# control.net
KiCad netlist of a schematic drawn in EAGLE
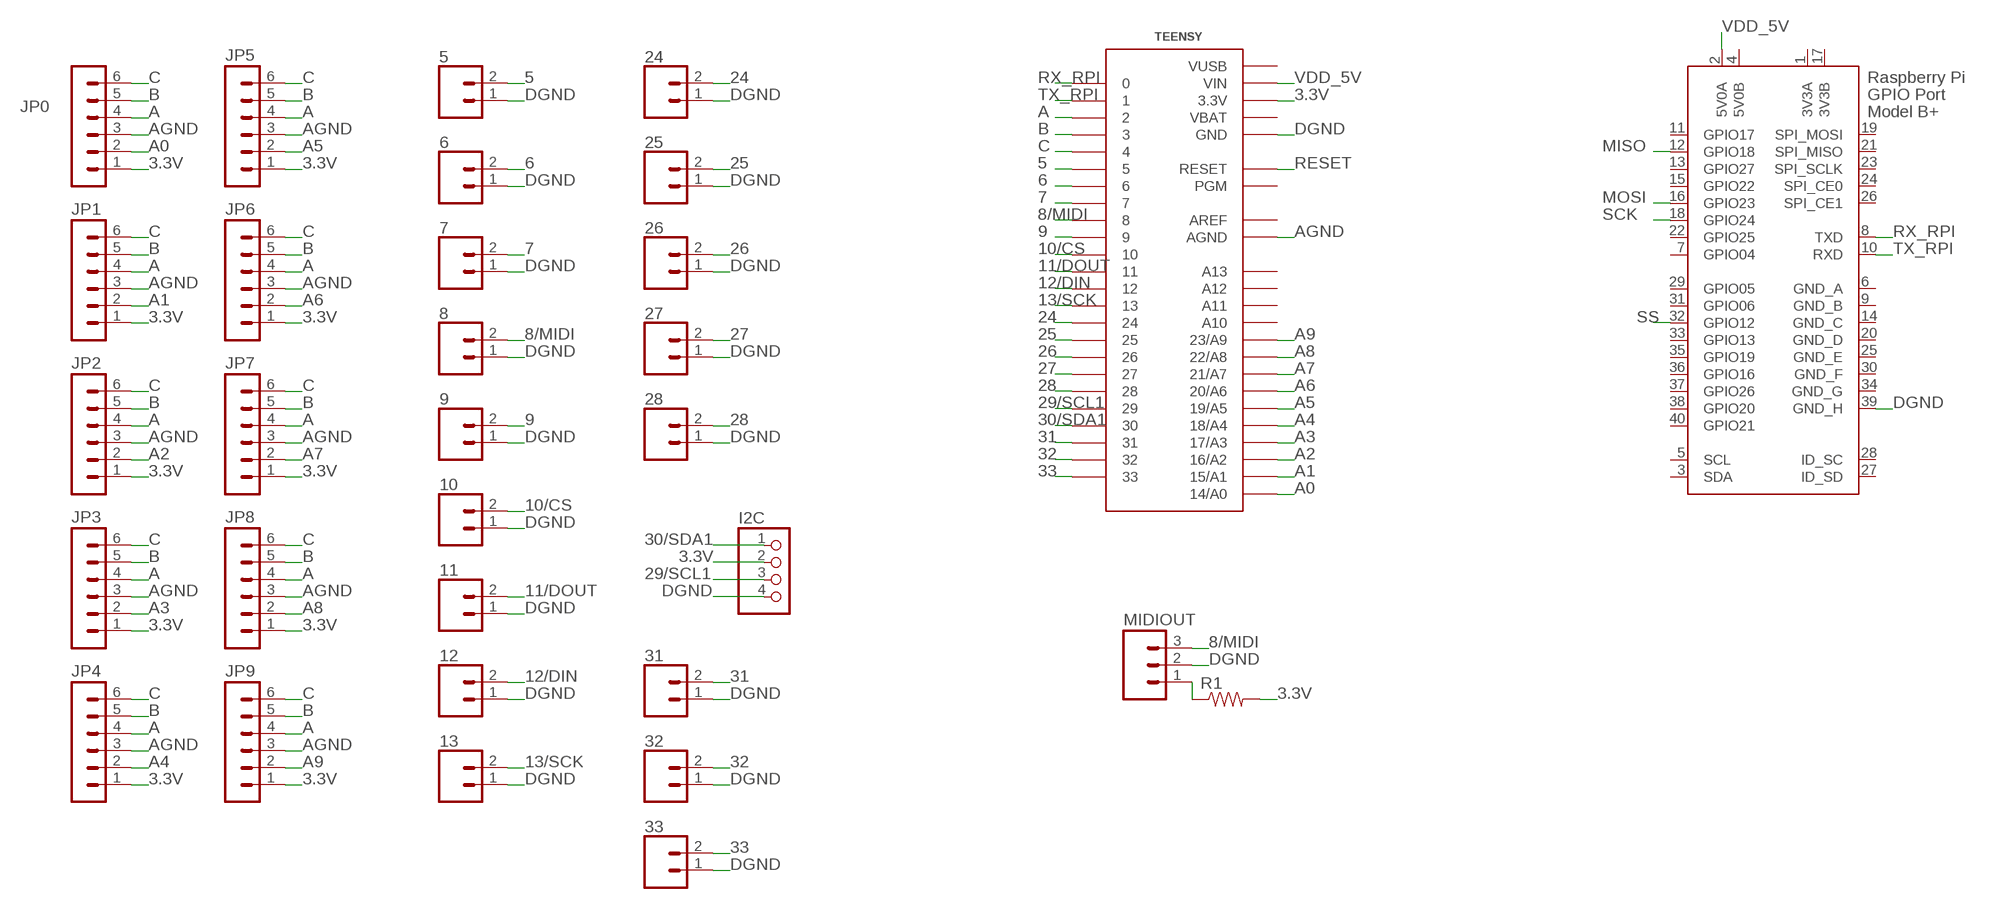
[diagram p0: schematic, sheet 1]

(export (version "E")
  (design (tool "Eeschema 10.0.6"))
  (components
    (comp (ref "5")
      (value "CONN_02")
      (footprint "eagle-import:1X02")
      (libsource (lib "eagle-import") (part "CONN_02"))
    )
    (comp (ref "6")
      (value "CONN_02")
      (footprint "eagle-import:1X02")
      (libsource (lib "eagle-import") (part "CONN_02"))
    )
    (comp (ref "7")
      (value "CONN_02")
      (footprint "eagle-import:1X02")
      (libsource (lib "eagle-import") (part "CONN_02"))
    )
    (comp (ref "8")
      (value "CONN_02")
      (footprint "eagle-import:1X02")
      (libsource (lib "eagle-import") (part "CONN_02"))
    )
    (comp (ref "9")
      (value "CONN_02")
      (footprint "eagle-import:1X02")
      (libsource (lib "eagle-import") (part "CONN_02"))
    )
    (comp (ref "10")
      (value "CONN_02")
      (footprint "eagle-import:1X02")
      (libsource (lib "eagle-import") (part "CONN_02"))
    )
    (comp (ref "11")
      (value "CONN_02")
      (footprint "eagle-import:1X02")
      (libsource (lib "eagle-import") (part "CONN_02"))
    )
    (comp (ref "12")
      (value "CONN_02")
      (footprint "eagle-import:1X02")
      (libsource (lib "eagle-import") (part "CONN_02"))
    )
    (comp (ref "13")
      (value "CONN_02")
      (footprint "eagle-import:1X02")
      (libsource (lib "eagle-import") (part "CONN_02"))
    )
    (comp (ref "24")
      (value "CONN_02")
      (footprint "eagle-import:1X02")
      (libsource (lib "eagle-import") (part "CONN_02"))
    )
    (comp (ref "25")
      (value "CONN_02")
      (footprint "eagle-import:1X02")
      (libsource (lib "eagle-import") (part "CONN_02"))
    )
    (comp (ref "26")
      (value "CONN_02")
      (footprint "eagle-import:1X02")
      (libsource (lib "eagle-import") (part "CONN_02"))
    )
    (comp (ref "27")
      (value "CONN_02")
      (footprint "eagle-import:1X02")
      (libsource (lib "eagle-import") (part "CONN_02"))
    )
    (comp (ref "28")
      (value "CONN_02")
      (footprint "eagle-import:1X02")
      (libsource (lib "eagle-import") (part "CONN_02"))
    )
    (comp (ref "31")
      (value "CONN_02")
      (footprint "eagle-import:1X02")
      (libsource (lib "eagle-import") (part "CONN_02"))
    )
    (comp (ref "32")
      (value "CONN_02")
      (footprint "eagle-import:1X02")
      (libsource (lib "eagle-import") (part "CONN_02"))
    )
    (comp (ref "33")
      (value "CONN_02")
      (footprint "eagle-import:1X02")
      (libsource (lib "eagle-import") (part "CONN_02"))
    )
    (comp (ref "I2C")
      (value "PINHD-1X4")
      (footprint "eagle-import:1X04")
      (libsource (lib "eagle-import") (part "PINHD-1X4"))
    )
    (comp (ref "JP0")
      (value "MA06-1")
      (footprint "eagle-import:MA06-1")
      (libsource (lib "eagle-import") (part "MA06-1"))
    )
    (comp (ref "JP1")
      (value "MA06-1")
      (footprint "eagle-import:MA06-1")
      (libsource (lib "eagle-import") (part "MA06-1"))
    )
    (comp (ref "JP2")
      (value "MA06-1")
      (footprint "eagle-import:MA06-1")
      (libsource (lib "eagle-import") (part "MA06-1"))
    )
    (comp (ref "JP3")
      (value "MA06-1")
      (footprint "eagle-import:MA06-1")
      (libsource (lib "eagle-import") (part "MA06-1"))
    )
    (comp (ref "JP4")
      (value "MA06-1")
      (footprint "eagle-import:MA06-1")
      (libsource (lib "eagle-import") (part "MA06-1"))
    )
    (comp (ref "JP5")
      (value "MA06-1")
      (footprint "eagle-import:MA06-1")
      (libsource (lib "eagle-import") (part "MA06-1"))
    )
    (comp (ref "JP6")
      (value "MA06-1")
      (footprint "eagle-import:MA06-1")
      (libsource (lib "eagle-import") (part "MA06-1"))
    )
    (comp (ref "JP7")
      (value "MA06-1")
      (footprint "eagle-import:MA06-1")
      (libsource (lib "eagle-import") (part "MA06-1"))
    )
    (comp (ref "JP8")
      (value "MA06-1")
      (footprint "eagle-import:MA06-1")
      (libsource (lib "eagle-import") (part "MA06-1"))
    )
    (comp (ref "JP9")
      (value "MA06-1")
      (footprint "eagle-import:MA06-1")
      (libsource (lib "eagle-import") (part "MA06-1"))
    )
    (comp (ref "MIDIOUT")
      (value "M03PTH")
      (footprint "eagle-import:1X03")
      (libsource (lib "eagle-import") (part "M03PTH"))
    )
    (comp (ref "R1")
      (value "RESISTORAXIAL-0.3")
      (footprint "eagle-import:AXIAL-0.3")
      (libsource (lib "eagle-import") (part "RESISTORAXIAL-0.3"))
    )
    (comp (ref "TEENSY")
      (value "TEENSY_3.0_ALLPINS")
      (footprint "eagle-import:TEENSY_3.0_ALLPINS")
      (libsource (lib "eagle-import") (part "TEENSY_3.0_ALLPINS"))
    )
    (comp (ref "X1")
      (value "RASPI_BOARD_B+#_H")
      (footprint "eagle-import:RASPI_BOARD_B+HAT")
      (libsource (lib "eagle-import") (part "RASPI_BOARD_B+#_H"))
    )
  )
  (nets
    (net (code "1") (name "/3.3V") (class "Default")
      (node (ref "I2C") (pin "2") (pinfunction "2_2") (pintype "passive"))
      (node (ref "JP0") (pin "1") (pinfunction "1_1") (pintype "passive"))
      (node (ref "JP1") (pin "1") (pinfunction "1_1") (pintype "passive"))
      (node (ref "JP2") (pin "1") (pinfunction "1_1") (pintype "passive"))
      (node (ref "JP3") (pin "1") (pinfunction "1_1") (pintype "passive"))
      (node (ref "JP4") (pin "1") (pinfunction "1_1") (pintype "passive"))
      (node (ref "JP5") (pin "1") (pinfunction "1_1") (pintype "passive"))
      (node (ref "JP6") (pin "1") (pinfunction "1_1") (pintype "passive"))
      (node (ref "JP7") (pin "1") (pinfunction "1_1") (pintype "passive"))
      (node (ref "JP8") (pin "1") (pinfunction "1_1") (pintype "passive"))
      (node (ref "JP9") (pin "1") (pinfunction "1_1") (pintype "passive"))
      (node (ref "R1") (pin "P$2") (pinfunction "2_P$2") (pintype "passive"))
      (node (ref "TEENSY") (pin "3.3V") (pinfunction "3.3V_3.3V") (pintype "power_in"))
      (node (ref "TEENSY") (pin "3.3V1") (pinfunction "3.3V_3.3V1") (pintype "power_in"))
      (node (ref "TEENSY") (pin "3.3V2") (pinfunction "3.3V_3.3V2") (pintype "power_in"))
    )
    (net (code "2") (name "/3V3A") (class "Default")
      (node (ref "X1") (pin "1") (pinfunction "3V3A_1") (pintype "power_in"))
    )
    (net (code "3") (name "/3V3B") (class "Default")
      (node (ref "X1") (pin "17") (pinfunction "3V3B_17") (pintype "power_in"))
    )
    (net (code "4") (name "/5") (class "Default")
      (node (ref "5") (pin "2") (pinfunction "2_2") (pintype "passive"))
      (node (ref "TEENSY") (pin "5") (pinfunction "5_5") (pintype "bidirectional"))
    )
    (net (code "5") (name "/5V0B") (class "Default")
      (node (ref "X1") (pin "4") (pinfunction "5V0B_4") (pintype "power_in"))
    )
    (net (code "6") (name "/6") (class "Default")
      (node (ref "6") (pin "2") (pinfunction "2_2") (pintype "passive"))
      (node (ref "TEENSY") (pin "6") (pinfunction "6_6") (pintype "bidirectional"))
    )
    (net (code "7") (name "/7") (class "Default")
      (node (ref "7") (pin "2") (pinfunction "2_2") (pintype "passive"))
      (node (ref "TEENSY") (pin "7") (pinfunction "7_7") (pintype "bidirectional"))
    )
    (net (code "8") (name "/8{slash}MIDI") (class "Default")
      (node (ref "8") (pin "2") (pinfunction "2_2") (pintype "passive"))
      (node (ref "MIDIOUT") (pin "3") (pinfunction "3_3") (pintype "passive"))
      (node (ref "TEENSY") (pin "8") (pinfunction "8_8") (pintype "bidirectional"))
    )
    (net (code "9") (name "/9") (class "Default")
      (node (ref "9") (pin "2") (pinfunction "2_2") (pintype "passive"))
      (node (ref "TEENSY") (pin "9") (pinfunction "9_9") (pintype "bidirectional"))
    )
    (net (code "10") (name "/10{slash}CS") (class "Default")
      (node (ref "10") (pin "2") (pinfunction "2_2") (pintype "passive"))
      (node (ref "TEENSY") (pin "10") (pinfunction "10_10") (pintype "bidirectional"))
    )
    (net (code "11") (name "/11{slash}DOUT") (class "Default")
      (node (ref "11") (pin "2") (pinfunction "2_2") (pintype "passive"))
      (node (ref "TEENSY") (pin "11") (pinfunction "11_11") (pintype "bidirectional"))
    )
    (net (code "12") (name "/12{slash}DIN") (class "Default")
      (node (ref "12") (pin "2") (pinfunction "2_2") (pintype "passive"))
      (node (ref "TEENSY") (pin "12") (pinfunction "12_12") (pintype "bidirectional"))
    )
    (net (code "13") (name "/13{slash}SCK") (class "Default")
      (node (ref "13") (pin "2") (pinfunction "2_2") (pintype "passive"))
      (node (ref "TEENSY") (pin "13") (pinfunction "13_13") (pintype "bidirectional"))
    )
    (net (code "14") (name "/24") (class "Default")
      (node (ref "24") (pin "2") (pinfunction "2_2") (pintype "passive"))
      (node (ref "TEENSY") (pin "24") (pinfunction "24_24") (pintype "bidirectional"))
    )
    (net (code "15") (name "/25") (class "Default")
      (node (ref "25") (pin "2") (pinfunction "2_2") (pintype "passive"))
      (node (ref "TEENSY") (pin "25") (pinfunction "25_25") (pintype "bidirectional"))
    )
    (net (code "16") (name "/26") (class "Default")
      (node (ref "26") (pin "2") (pinfunction "2_2") (pintype "passive"))
      (node (ref "TEENSY") (pin "26") (pinfunction "26_26") (pintype "bidirectional"))
    )
    (net (code "17") (name "/27") (class "Default")
      (node (ref "27") (pin "2") (pinfunction "2_2") (pintype "passive"))
      (node (ref "TEENSY") (pin "27") (pinfunction "27_27") (pintype "bidirectional"))
    )
    (net (code "18") (name "/28") (class "Default")
      (node (ref "28") (pin "2") (pinfunction "2_2") (pintype "passive"))
      (node (ref "TEENSY") (pin "28") (pinfunction "28_28") (pintype "bidirectional"))
    )
    (net (code "19") (name "/29{slash}SCL1") (class "Default")
      (node (ref "I2C") (pin "3") (pinfunction "3_3") (pintype "passive"))
      (node (ref "TEENSY") (pin "29") (pinfunction "29_29") (pintype "bidirectional"))
    )
    (net (code "20") (name "/30{slash}SDA1") (class "Default")
      (node (ref "I2C") (pin "1") (pinfunction "1_1") (pintype "passive"))
      (node (ref "TEENSY") (pin "30") (pinfunction "30_30") (pintype "bidirectional"))
    )
    (net (code "21") (name "/31") (class "Default")
      (node (ref "31") (pin "2") (pinfunction "2_2") (pintype "passive"))
      (node (ref "TEENSY") (pin "31") (pinfunction "31_31") (pintype "bidirectional"))
    )
    (net (code "22") (name "/32") (class "Default")
      (node (ref "32") (pin "2") (pinfunction "2_2") (pintype "passive"))
      (node (ref "TEENSY") (pin "32") (pinfunction "32_32") (pintype "bidirectional"))
    )
    (net (code "23") (name "/33") (class "Default")
      (node (ref "33") (pin "2") (pinfunction "2_2") (pintype "passive"))
      (node (ref "TEENSY") (pin "33") (pinfunction "33_33") (pintype "bidirectional"))
    )
    (net (code "24") (name "/A") (class "Default")
      (node (ref "JP0") (pin "4") (pinfunction "4_4") (pintype "passive"))
      (node (ref "JP1") (pin "4") (pinfunction "4_4") (pintype "passive"))
      (node (ref "JP2") (pin "4") (pinfunction "4_4") (pintype "passive"))
      (node (ref "JP3") (pin "4") (pinfunction "4_4") (pintype "passive"))
      (node (ref "JP4") (pin "4") (pinfunction "4_4") (pintype "passive"))
      (node (ref "JP5") (pin "4") (pinfunction "4_4") (pintype "passive"))
      (node (ref "JP6") (pin "4") (pinfunction "4_4") (pintype "passive"))
      (node (ref "JP7") (pin "4") (pinfunction "4_4") (pintype "passive"))
      (node (ref "JP8") (pin "4") (pinfunction "4_4") (pintype "passive"))
      (node (ref "JP9") (pin "4") (pinfunction "4_4") (pintype "passive"))
      (node (ref "TEENSY") (pin "2") (pinfunction "2_2") (pintype "bidirectional"))
    )
    (net (code "25") (name "/A0") (class "Default")
      (node (ref "JP0") (pin "2") (pinfunction "2_2") (pintype "passive"))
      (node (ref "TEENSY") (pin "14/A0") (pinfunction "14/A0_14/A0") (pintype "bidirectional"))
    )
    (net (code "26") (name "/A1") (class "Default")
      (node (ref "JP1") (pin "2") (pinfunction "2_2") (pintype "passive"))
      (node (ref "TEENSY") (pin "15/A1") (pinfunction "15/A1_15/A1") (pintype "bidirectional"))
    )
    (net (code "27") (name "/A2") (class "Default")
      (node (ref "JP2") (pin "2") (pinfunction "2_2") (pintype "passive"))
      (node (ref "TEENSY") (pin "16/A2") (pinfunction "16/A2_16/A2") (pintype "bidirectional"))
    )
    (net (code "28") (name "/A3") (class "Default")
      (node (ref "JP3") (pin "2") (pinfunction "2_2") (pintype "passive"))
      (node (ref "TEENSY") (pin "17/A3") (pinfunction "17/A3_17/A3") (pintype "bidirectional"))
    )
    (net (code "29") (name "/A4") (class "Default")
      (node (ref "JP4") (pin "2") (pinfunction "2_2") (pintype "passive"))
      (node (ref "TEENSY") (pin "18/A4") (pinfunction "18/A4_18/A4") (pintype "bidirectional"))
    )
    (net (code "30") (name "/A5") (class "Default")
      (node (ref "JP5") (pin "2") (pinfunction "2_2") (pintype "passive"))
      (node (ref "TEENSY") (pin "19/A5") (pinfunction "19/A5_19/A5") (pintype "bidirectional"))
    )
    (net (code "31") (name "/A6") (class "Default")
      (node (ref "JP6") (pin "2") (pinfunction "2_2") (pintype "passive"))
      (node (ref "TEENSY") (pin "20/A6") (pinfunction "20/A6_20/A6") (pintype "bidirectional"))
    )
    (net (code "32") (name "/A7") (class "Default")
      (node (ref "JP7") (pin "2") (pinfunction "2_2") (pintype "passive"))
      (node (ref "TEENSY") (pin "21/A7") (pinfunction "21/A7_21/A7") (pintype "bidirectional"))
    )
    (net (code "33") (name "/A8") (class "Default")
      (node (ref "JP8") (pin "2") (pinfunction "2_2") (pintype "passive"))
      (node (ref "TEENSY") (pin "22/A8") (pinfunction "22/A8_22/A8") (pintype "bidirectional"))
    )
    (net (code "34") (name "/A9") (class "Default")
      (node (ref "JP9") (pin "2") (pinfunction "2_2") (pintype "passive"))
      (node (ref "TEENSY") (pin "23/A9") (pinfunction "23/A9_23/A9") (pintype "bidirectional"))
    )
    (net (code "35") (name "/AGND") (class "Default")
      (node (ref "JP0") (pin "3") (pinfunction "3_3") (pintype "passive"))
      (node (ref "JP1") (pin "3") (pinfunction "3_3") (pintype "passive"))
      (node (ref "JP2") (pin "3") (pinfunction "3_3") (pintype "passive"))
      (node (ref "JP3") (pin "3") (pinfunction "3_3") (pintype "passive"))
      (node (ref "JP4") (pin "3") (pinfunction "3_3") (pintype "passive"))
      (node (ref "JP5") (pin "3") (pinfunction "3_3") (pintype "passive"))
      (node (ref "JP6") (pin "3") (pinfunction "3_3") (pintype "passive"))
      (node (ref "JP7") (pin "3") (pinfunction "3_3") (pintype "passive"))
      (node (ref "JP8") (pin "3") (pinfunction "3_3") (pintype "passive"))
      (node (ref "JP9") (pin "3") (pinfunction "3_3") (pintype "passive"))
      (node (ref "TEENSY") (pin "AGND") (pinfunction "AGND_AGND") (pintype "power_in"))
    )
    (net (code "36") (name "/AREF") (class "Default")
      (node (ref "TEENSY") (pin "AREF") (pinfunction "AREF_AREF") (pintype "power_in"))
    )
    (net (code "37") (name "/B") (class "Default")
      (node (ref "JP0") (pin "5") (pinfunction "5_5") (pintype "passive"))
      (node (ref "JP1") (pin "5") (pinfunction "5_5") (pintype "passive"))
      (node (ref "JP2") (pin "5") (pinfunction "5_5") (pintype "passive"))
      (node (ref "JP3") (pin "5") (pinfunction "5_5") (pintype "passive"))
      (node (ref "JP4") (pin "5") (pinfunction "5_5") (pintype "passive"))
      (node (ref "JP5") (pin "5") (pinfunction "5_5") (pintype "passive"))
      (node (ref "JP6") (pin "5") (pinfunction "5_5") (pintype "passive"))
      (node (ref "JP7") (pin "5") (pinfunction "5_5") (pintype "passive"))
      (node (ref "JP8") (pin "5") (pinfunction "5_5") (pintype "passive"))
      (node (ref "JP9") (pin "5") (pinfunction "5_5") (pintype "passive"))
      (node (ref "TEENSY") (pin "3") (pinfunction "3_3") (pintype "bidirectional"))
    )
    (net (code "38") (name "/C") (class "Default")
      (node (ref "JP0") (pin "6") (pinfunction "6_6") (pintype "passive"))
      (node (ref "JP1") (pin "6") (pinfunction "6_6") (pintype "passive"))
      (node (ref "JP2") (pin "6") (pinfunction "6_6") (pintype "passive"))
      (node (ref "JP3") (pin "6") (pinfunction "6_6") (pintype "passive"))
      (node (ref "JP4") (pin "6") (pinfunction "6_6") (pintype "passive"))
      (node (ref "JP5") (pin "6") (pinfunction "6_6") (pintype "passive"))
      (node (ref "JP6") (pin "6") (pinfunction "6_6") (pintype "passive"))
      (node (ref "JP7") (pin "6") (pinfunction "6_6") (pintype "passive"))
      (node (ref "JP8") (pin "6") (pinfunction "6_6") (pintype "passive"))
      (node (ref "JP9") (pin "6") (pinfunction "6_6") (pintype "passive"))
      (node (ref "TEENSY") (pin "4") (pinfunction "4_4") (pintype "bidirectional"))
    )
    (net (code "39") (name "/DGND") (class "Default")
      (node (ref "10") (pin "1") (pinfunction "1_1") (pintype "passive"))
      (node (ref "11") (pin "1") (pinfunction "1_1") (pintype "passive"))
      (node (ref "12") (pin "1") (pinfunction "1_1") (pintype "passive"))
      (node (ref "13") (pin "1") (pinfunction "1_1") (pintype "passive"))
      (node (ref "24") (pin "1") (pinfunction "1_1") (pintype "passive"))
      (node (ref "25") (pin "1") (pinfunction "1_1") (pintype "passive"))
      (node (ref "26") (pin "1") (pinfunction "1_1") (pintype "passive"))
      (node (ref "27") (pin "1") (pinfunction "1_1") (pintype "passive"))
      (node (ref "28") (pin "1") (pinfunction "1_1") (pintype "passive"))
      (node (ref "31") (pin "1") (pinfunction "1_1") (pintype "passive"))
      (node (ref "32") (pin "1") (pinfunction "1_1") (pintype "passive"))
      (node (ref "33") (pin "1") (pinfunction "1_1") (pintype "passive"))
      (node (ref "5") (pin "1") (pinfunction "1_1") (pintype "passive"))
      (node (ref "6") (pin "1") (pinfunction "1_1") (pintype "passive"))
      (node (ref "7") (pin "1") (pinfunction "1_1") (pintype "passive"))
      (node (ref "8") (pin "1") (pinfunction "1_1") (pintype "passive"))
      (node (ref "9") (pin "1") (pinfunction "1_1") (pintype "passive"))
      (node (ref "I2C") (pin "4") (pinfunction "4_4") (pintype "passive"))
      (node (ref "MIDIOUT") (pin "2") (pinfunction "2_2") (pintype "passive"))
      (node (ref "TEENSY") (pin "GND") (pinfunction "GND_GND") (pintype "power_in"))
      (node (ref "TEENSY") (pin "GND1") (pinfunction "GND_GND1") (pintype "power_in"))
      (node (ref "TEENSY") (pin "GND2") (pinfunction "GND_GND2") (pintype "power_in"))
      (node (ref "X1") (pin "39") (pinfunction "GND_H_39") (pintype "power_in"))
    )
    (net (code "40") (name "/GND_A") (class "Default")
      (node (ref "X1") (pin "6") (pinfunction "GND_A_6") (pintype "power_in"))
    )
    (net (code "41") (name "/GND_B") (class "Default")
      (node (ref "X1") (pin "9") (pinfunction "GND_B_9") (pintype "power_in"))
    )
    (net (code "42") (name "/GND_C") (class "Default")
      (node (ref "X1") (pin "14") (pinfunction "GND_C_14") (pintype "power_in"))
    )
    (net (code "43") (name "/GND_D") (class "Default")
      (node (ref "X1") (pin "20") (pinfunction "GND_D_20") (pintype "power_in"))
    )
    (net (code "44") (name "/GND_E") (class "Default")
      (node (ref "X1") (pin "25") (pinfunction "GND_E_25") (pintype "power_in"))
    )
    (net (code "45") (name "/GND_F") (class "Default")
      (node (ref "X1") (pin "30") (pinfunction "GND_F_30") (pintype "power_in"))
    )
    (net (code "46") (name "/GND_G") (class "Default")
      (node (ref "X1") (pin "34") (pinfunction "GND_G_34") (pintype "power_in"))
    )
    (net (code "47") (name "/MISO") (class "Default")
      (node (ref "X1") (pin "12") (pinfunction "GPIO18_12") (pintype "bidirectional"))
    )
    (net (code "48") (name "/MOSI") (class "Default")
      (node (ref "X1") (pin "16") (pinfunction "GPIO23_16") (pintype "bidirectional"))
    )
    (net (code "49") (name "/RESET") (class "Default")
      (node (ref "TEENSY") (pin "RESET") (pinfunction "RESET_RESET") (pintype "bidirectional"))
    )
    (net (code "50") (name "/RX_RPI") (class "Default")
      (node (ref "TEENSY") (pin "0") (pinfunction "0_0") (pintype "bidirectional"))
      (node (ref "X1") (pin "8") (pinfunction "TXD_8") (pintype "bidirectional"))
    )
    (net (code "51") (name "/SCK") (class "Default")
      (node (ref "X1") (pin "18") (pinfunction "GPIO24_18") (pintype "bidirectional"))
    )
    (net (code "53") (name "/SS") (class "Default")
      (node (ref "X1") (pin "32") (pinfunction "GPIO12_32") (pintype "no_connect"))
    )
    (net (code "54") (name "/TX_RPI") (class "Default")
      (node (ref "TEENSY") (pin "1") (pinfunction "1_1") (pintype "bidirectional"))
      (node (ref "X1") (pin "10") (pinfunction "RXD_10") (pintype "bidirectional"))
    )
    (net (code "55") (name "/VBAT") (class "Default")
      (node (ref "TEENSY") (pin "VBAT") (pinfunction "VBAT_VBAT") (pintype "power_in"))
    )
    (net (code "56") (name "/VDD_5V") (class "Default")
      (node (ref "TEENSY") (pin "VIN") (pinfunction "VIN_VIN") (pintype "power_in"))
      (node (ref "X1") (pin "2") (pinfunction "5V0A_2") (pintype "power_in"))
    )
    (net (code "57") (name "/VUSB") (class "Default")
      (node (ref "TEENSY") (pin "VUSB") (pinfunction "VUSB_VUSB") (pintype "power_in"))
    )
    (net (code "58") (name "Net-(R1-1)") (class "Default")
      (node (ref "MIDIOUT") (pin "1") (pinfunction "1_1") (pintype "passive"))
      (node (ref "R1") (pin "P$1") (pinfunction "1_P$1") (pintype "passive"))
    )
    (net (code "59") (name "unconnected-(TEENSY-PadA10)") (class "Default")
      (node (ref "TEENSY") (pin "A10") (pinfunction "A10_A10") (pintype "bidirectional"))
    )
    (net (code "60") (name "unconnected-(TEENSY-PadA11)") (class "Default")
      (node (ref "TEENSY") (pin "A11") (pinfunction "A11_A11") (pintype "bidirectional"))
    )
    (net (code "61") (name "unconnected-(TEENSY-PadA12)") (class "Default")
      (node (ref "TEENSY") (pin "A12") (pinfunction "A12_A12") (pintype "bidirectional"))
    )
    (net (code "62") (name "unconnected-(TEENSY-PadA13)") (class "Default")
      (node (ref "TEENSY") (pin "A13") (pinfunction "A13_A13") (pintype "bidirectional"))
    )
    (net (code "63") (name "unconnected-(TEENSY-PadPGM)") (class "Default")
      (node (ref "TEENSY") (pin "PGM") (pinfunction "PGM_PGM") (pintype "bidirectional"))
    )
    (net (code "64") (name "unconnected-(X1-GPIO04-Pad7)") (class "Default")
      (node (ref "X1") (pin "7") (pinfunction "GPIO04_7") (pintype "bidirectional"))
    )
    (net (code "65") (name "unconnected-(X1-GPIO05-Pad29)") (class "Default")
      (node (ref "X1") (pin "29") (pinfunction "GPIO05_29") (pintype "no_connect"))
    )
    (net (code "66") (name "unconnected-(X1-GPIO06-Pad31)") (class "Default")
      (node (ref "X1") (pin "31") (pinfunction "GPIO06_31") (pintype "no_connect"))
    )
    (net (code "67") (name "unconnected-(X1-GPIO13-Pad33)") (class "Default")
      (node (ref "X1") (pin "33") (pinfunction "GPIO13_33") (pintype "no_connect"))
    )
    (net (code "68") (name "unconnected-(X1-GPIO16-Pad36)") (class "Default")
      (node (ref "X1") (pin "36") (pinfunction "GPIO16_36") (pintype "no_connect"))
    )
    (net (code "69") (name "unconnected-(X1-GPIO17-Pad11)") (class "Default")
      (node (ref "X1") (pin "11") (pinfunction "GPIO17_11") (pintype "bidirectional"))
    )
    (net (code "70") (name "unconnected-(X1-GPIO19-Pad35)") (class "Default")
      (node (ref "X1") (pin "35") (pinfunction "GPIO19_35") (pintype "no_connect"))
    )
    (net (code "71") (name "unconnected-(X1-GPIO20-Pad38)") (class "Default")
      (node (ref "X1") (pin "38") (pinfunction "GPIO20_38") (pintype "no_connect"))
    )
    (net (code "72") (name "unconnected-(X1-GPIO21-Pad40)") (class "Default")
      (node (ref "X1") (pin "40") (pinfunction "GPIO21_40") (pintype "no_connect"))
    )
    (net (code "73") (name "unconnected-(X1-GPIO22-Pad15)") (class "Default")
      (node (ref "X1") (pin "15") (pinfunction "GPIO22_15") (pintype "bidirectional"))
    )
    (net (code "74") (name "unconnected-(X1-GPIO25-Pad22)") (class "Default")
      (node (ref "X1") (pin "22") (pinfunction "GPIO25_22") (pintype "bidirectional"))
    )
    (net (code "75") (name "unconnected-(X1-GPIO26-Pad37)") (class "Default")
      (node (ref "X1") (pin "37") (pinfunction "GPIO26_37") (pintype "no_connect"))
    )
    (net (code "76") (name "unconnected-(X1-GPIO27-Pad13)") (class "Default")
      (node (ref "X1") (pin "13") (pinfunction "GPIO27_13") (pintype "bidirectional"))
    )
    (net (code "77") (name "unconnected-(X1-ID_SC-Pad28)") (class "Default")
      (node (ref "X1") (pin "28") (pinfunction "ID_SC_28") (pintype "no_connect"))
    )
    (net (code "78") (name "unconnected-(X1-ID_SD-Pad27)") (class "Default")
      (node (ref "X1") (pin "27") (pinfunction "ID_SD_27") (pintype "no_connect"))
    )
    (net (code "79") (name "unconnected-(X1-SCL-Pad5)") (class "Default")
      (node (ref "X1") (pin "5") (pinfunction "SCL_5") (pintype "bidirectional"))
    )
    (net (code "80") (name "unconnected-(X1-SDA-Pad3)") (class "Default")
      (node (ref "X1") (pin "3") (pinfunction "SDA_3") (pintype "bidirectional"))
    )
    (net (code "81") (name "unconnected-(X1-SPI_CE0-Pad24)") (class "Default")
      (node (ref "X1") (pin "24") (pinfunction "SPI_CE0_24") (pintype "bidirectional"))
    )
    (net (code "82") (name "unconnected-(X1-SPI_CE1-Pad26)") (class "Default")
      (node (ref "X1") (pin "26") (pinfunction "SPI_CE1_26") (pintype "bidirectional"))
    )
    (net (code "83") (name "unconnected-(X1-SPI_MISO-Pad21)") (class "Default")
      (node (ref "X1") (pin "21") (pinfunction "SPI_MISO_21") (pintype "bidirectional"))
    )
    (net (code "84") (name "unconnected-(X1-SPI_MOSI-Pad19)") (class "Default")
      (node (ref "X1") (pin "19") (pinfunction "SPI_MOSI_19") (pintype "bidirectional"))
    )
    (net (code "85") (name "unconnected-(X1-SPI_SCLK-Pad23)") (class "Default")
      (node (ref "X1") (pin "23") (pinfunction "SPI_SCLK_23") (pintype "bidirectional"))
    )
  )
)
